# p2cled-001.net
KiCad netlist of a schematic drawn in EAGLE
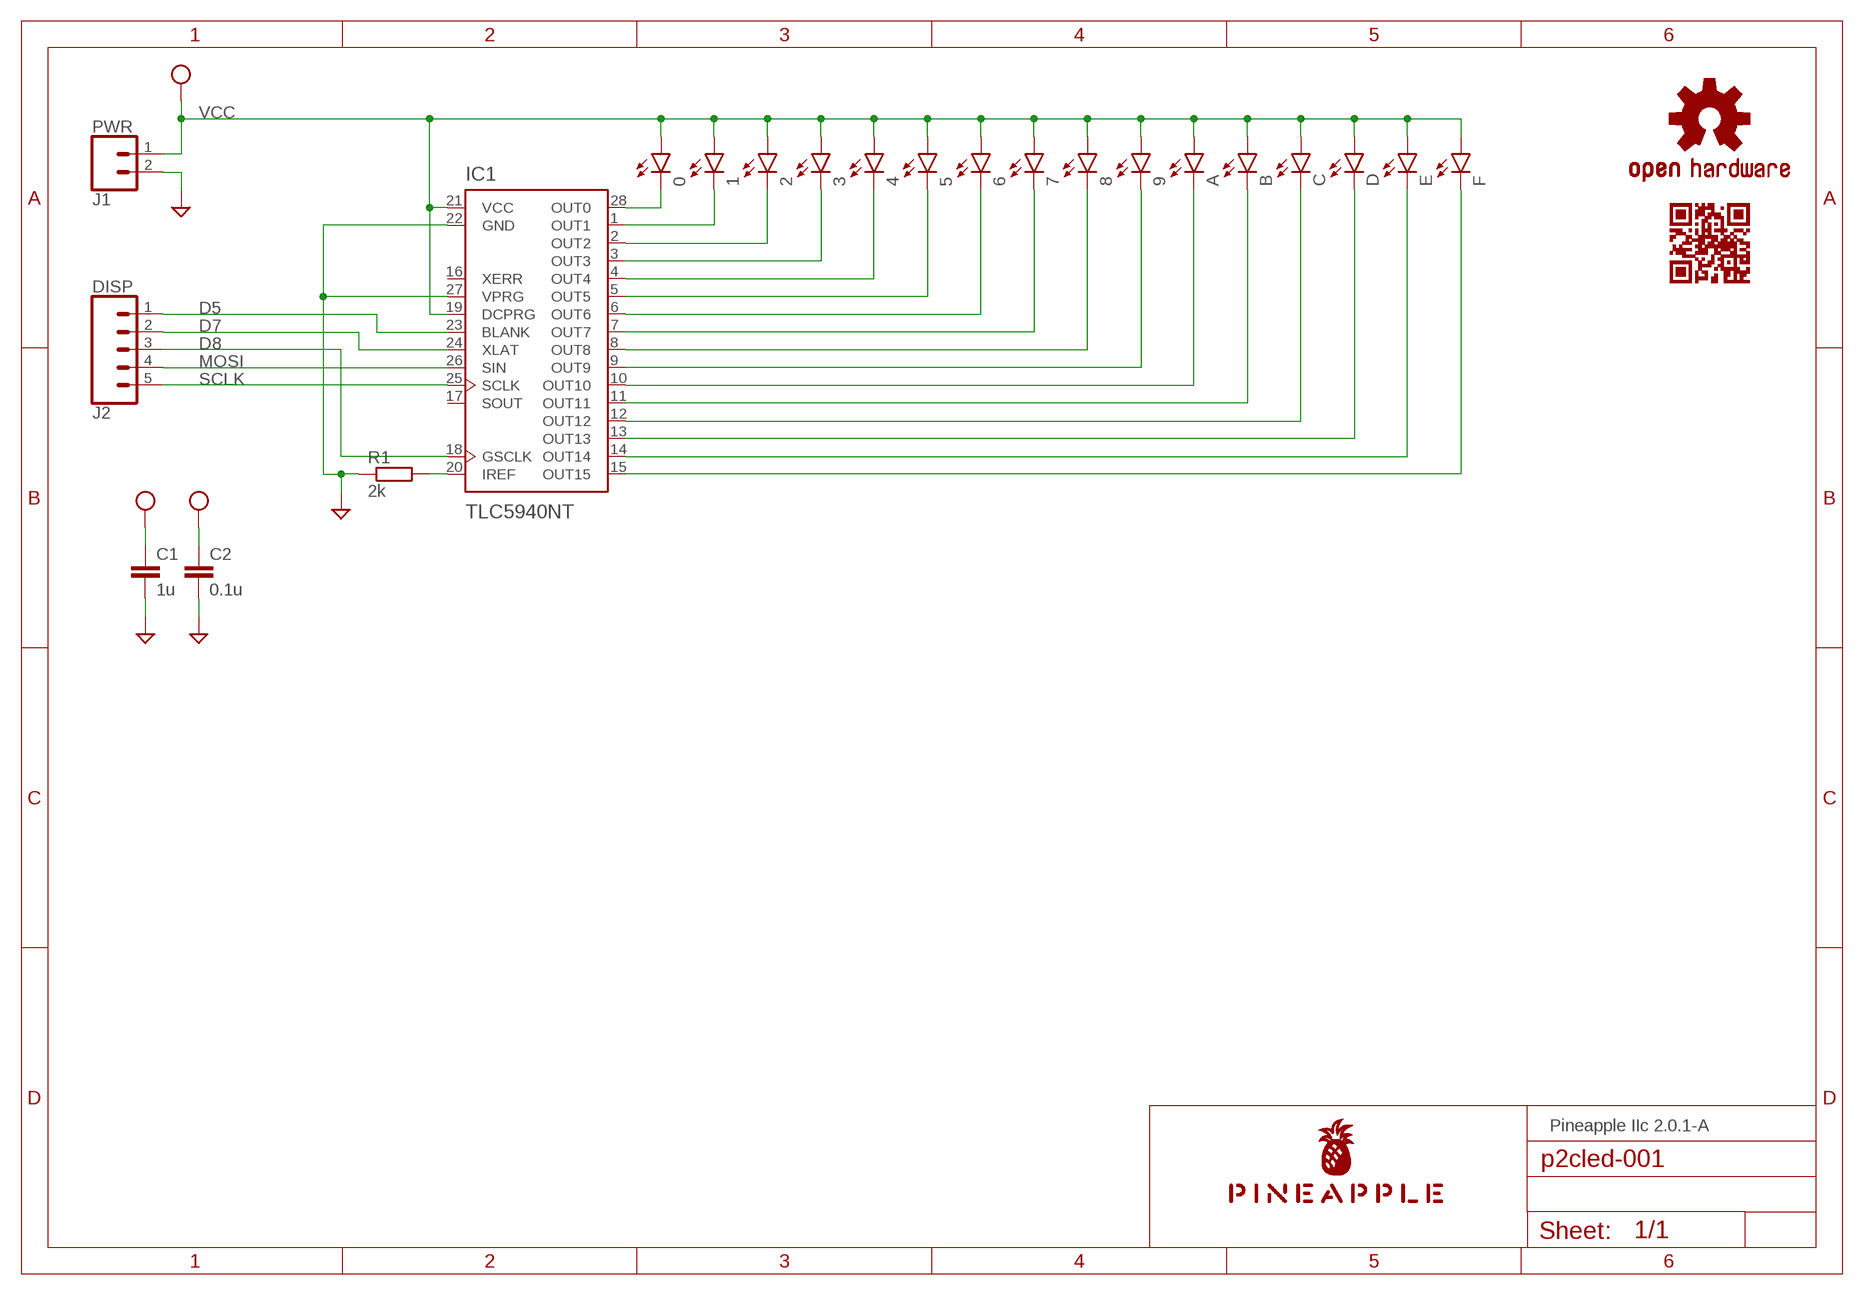
[diagram p0: schematic, sheet 1]

(export (version "E")
  (design (tool "Eeschema 10.0.6"))
  (components
    (comp (ref "0")
      (value "LEDB152")
      (footprint "eagle-import:Q62902-B152")
      (libsource (lib "eagle-import") (part "LEDB152"))
    )
    (comp (ref "1")
      (value "LEDB152")
      (footprint "eagle-import:Q62902-B152")
      (libsource (lib "eagle-import") (part "LEDB152"))
    )
    (comp (ref "2")
      (value "LEDB152")
      (footprint "eagle-import:Q62902-B152")
      (libsource (lib "eagle-import") (part "LEDB152"))
    )
    (comp (ref "3")
      (value "LEDB152")
      (footprint "eagle-import:Q62902-B152")
      (libsource (lib "eagle-import") (part "LEDB152"))
    )
    (comp (ref "4")
      (value "LEDB152")
      (footprint "eagle-import:Q62902-B152")
      (libsource (lib "eagle-import") (part "LEDB152"))
    )
    (comp (ref "5")
      (value "LEDB152")
      (footprint "eagle-import:Q62902-B152")
      (libsource (lib "eagle-import") (part "LEDB152"))
    )
    (comp (ref "6")
      (value "LEDB152")
      (footprint "eagle-import:Q62902-B152")
      (libsource (lib "eagle-import") (part "LEDB152"))
    )
    (comp (ref "7")
      (value "LEDB152")
      (footprint "eagle-import:Q62902-B152")
      (libsource (lib "eagle-import") (part "LEDB152"))
    )
    (comp (ref "8")
      (value "LEDB152")
      (footprint "eagle-import:Q62902-B152")
      (libsource (lib "eagle-import") (part "LEDB152"))
    )
    (comp (ref "9")
      (value "LEDB152")
      (footprint "eagle-import:Q62902-B152")
      (libsource (lib "eagle-import") (part "LEDB152"))
    )
    (comp (ref "A")
      (value "LEDB152")
      (footprint "eagle-import:Q62902-B152")
      (libsource (lib "eagle-import") (part "LEDB152"))
    )
    (comp (ref "B")
      (value "LEDB152")
      (footprint "eagle-import:Q62902-B152")
      (libsource (lib "eagle-import") (part "LEDB152"))
    )
    (comp (ref "C")
      (value "LEDB152")
      (footprint "eagle-import:Q62902-B152")
      (libsource (lib "eagle-import") (part "LEDB152"))
    )
    (comp (ref "C1")
      (value "1u")
      (footprint "eagle-import:C025-024X044")
      (libsource (lib "eagle-import") (part "C-EU025-024X044"))
    )
    (comp (ref "C2")
      (value "0.1u")
      (footprint "eagle-import:C025-024X044")
      (libsource (lib "eagle-import") (part "C-EU025-024X044"))
    )
    (comp (ref "D")
      (value "LEDB152")
      (footprint "eagle-import:Q62902-B152")
      (libsource (lib "eagle-import") (part "LEDB152"))
    )
    (comp (ref "E")
      (value "LEDB152")
      (footprint "eagle-import:Q62902-B152")
      (libsource (lib "eagle-import") (part "LEDB152"))
    )
    (comp (ref "F")
      (value "LEDB152")
      (footprint "eagle-import:Q62902-B152")
      (libsource (lib "eagle-import") (part "LEDB152"))
    )
    (comp (ref "IC1")
      (value "TLC5940NT")
      (footprint "eagle-import:DIL28-3")
      (libsource (lib "eagle-import") (part "TLC5940NT"))
    )
    (comp (ref "J1")
      (value "PWR")
      (footprint "eagle-import:JST-2-PTH")
      (libsource (lib "eagle-import") (part "CONN_02JST-PTH-2"))
    )
    (comp (ref "J2")
      (value "DISP")
      (footprint "eagle-import:JST-5-PTH")
      (libsource (lib "eagle-import") (part "CONN_05JST"))
    )
    (comp (ref "LOGO1")
      (value "OSHW-LOGOS-COPPER")
      (footprint "eagle-import:OSHW-LOGO-S_COPPER")
      (libsource (lib "eagle-import") (part "OSHW-LOGOS-COPPER"))
    )
    (comp (ref "R1")
      (value "2k")
      (footprint "eagle-import:0204_5")
      (libsource (lib "eagle-import") (part "R-EU_0204/5"))
    )
    (comp (ref "U$1")
      (value "PINEAPPLE450_SILK")
      (footprint "eagle-import:PINEAPPLE450_SILK")
      (libsource (lib "eagle-import") (part "PINEAPPLE450_SILK"))
    )
    (comp (ref "U$4")
      (value "CARDQRCODE450_SILK")
      (footprint "eagle-import:CARDQRCODE450_SILK")
      (libsource (lib "eagle-import") (part "CARDQRCODE450_SILK"))
    )
  )
  (nets
    (net (code "1") (name "/D5") (class "Default")
      (node (ref "IC1") (pin "23") (pinfunction "BLANK_23") (pintype "input"))
      (node (ref "J2") (pin "1") (pinfunction "1_1") (pintype "passive"))
    )
    (net (code "2") (name "/D7") (class "Default")
      (node (ref "IC1") (pin "24") (pinfunction "XLAT_24") (pintype "input"))
      (node (ref "J2") (pin "2") (pinfunction "2_2") (pintype "passive"))
    )
    (net (code "3") (name "/D8") (class "Default")
      (node (ref "IC1") (pin "18") (pinfunction "GSCLK_18") (pintype "input"))
      (node (ref "J2") (pin "3") (pinfunction "3_3") (pintype "passive"))
    )
    (net (code "4") (name "/MOSI") (class "Default")
      (node (ref "IC1") (pin "26") (pinfunction "SIN_26") (pintype "input"))
      (node (ref "J2") (pin "4") (pinfunction "4_4") (pintype "passive"))
    )
    (net (code "5") (name "/SCLK") (class "Default")
      (node (ref "IC1") (pin "25") (pinfunction "SCLK_25") (pintype "input"))
      (node (ref "J2") (pin "5") (pinfunction "5_5") (pintype "passive"))
    )
    (net (code "6") (name "GND") (class "Default")
      (node (ref "C1") (pin "2") (pinfunction "2_2") (pintype "passive"))
      (node (ref "C2") (pin "2") (pinfunction "2_2") (pintype "passive"))
      (node (ref "IC1") (pin "22") (pinfunction "GND_22") (pintype "power_in"))
      (node (ref "IC1") (pin "27") (pinfunction "VPRG_27") (pintype "input"))
      (node (ref "J1") (pin "2") (pinfunction "2_2") (pintype "passive"))
      (node (ref "R1") (pin "1") (pinfunction "1_1") (pintype "passive"))
    )
    (net (code "7") (name "Net-(0-C)") (class "Default")
      (node (ref "0") (pin "K") (pinfunction "C_K") (pintype "passive"))
      (node (ref "IC1") (pin "28") (pinfunction "OUT0_28") (pintype "output"))
    )
    (net (code "8") (name "Net-(1-C)") (class "Default")
      (node (ref "1") (pin "K") (pinfunction "C_K") (pintype "passive"))
      (node (ref "IC1") (pin "1") (pinfunction "OUT1_1") (pintype "output"))
    )
    (net (code "9") (name "Net-(2-C)") (class "Default")
      (node (ref "2") (pin "K") (pinfunction "C_K") (pintype "passive"))
      (node (ref "IC1") (pin "2") (pinfunction "OUT2_2") (pintype "output"))
    )
    (net (code "10") (name "Net-(3-C)") (class "Default")
      (node (ref "3") (pin "K") (pinfunction "C_K") (pintype "passive"))
      (node (ref "IC1") (pin "3") (pinfunction "OUT3_3") (pintype "output"))
    )
    (net (code "11") (name "Net-(4-C)") (class "Default")
      (node (ref "4") (pin "K") (pinfunction "C_K") (pintype "passive"))
      (node (ref "IC1") (pin "4") (pinfunction "OUT4_4") (pintype "output"))
    )
    (net (code "12") (name "Net-(5-C)") (class "Default")
      (node (ref "5") (pin "K") (pinfunction "C_K") (pintype "passive"))
      (node (ref "IC1") (pin "5") (pinfunction "OUT5_5") (pintype "output"))
    )
    (net (code "13") (name "Net-(6-C)") (class "Default")
      (node (ref "6") (pin "K") (pinfunction "C_K") (pintype "passive"))
      (node (ref "IC1") (pin "6") (pinfunction "OUT6_6") (pintype "output"))
    )
    (net (code "14") (name "Net-(7-C)") (class "Default")
      (node (ref "7") (pin "K") (pinfunction "C_K") (pintype "passive"))
      (node (ref "IC1") (pin "7") (pinfunction "OUT7_7") (pintype "output"))
    )
    (net (code "15") (name "Net-(8-C)") (class "Default")
      (node (ref "8") (pin "K") (pinfunction "C_K") (pintype "passive"))
      (node (ref "IC1") (pin "8") (pinfunction "OUT8_8") (pintype "output"))
    )
    (net (code "16") (name "Net-(9-C)") (class "Default")
      (node (ref "9") (pin "K") (pinfunction "C_K") (pintype "passive"))
      (node (ref "IC1") (pin "9") (pinfunction "OUT9_9") (pintype "output"))
    )
    (net (code "17") (name "Net-(A-C)") (class "Default")
      (node (ref "A") (pin "K") (pinfunction "C_K") (pintype "passive"))
      (node (ref "IC1") (pin "10") (pinfunction "OUT10_10") (pintype "output"))
    )
    (net (code "18") (name "Net-(B-C)") (class "Default")
      (node (ref "B") (pin "K") (pinfunction "C_K") (pintype "passive"))
      (node (ref "IC1") (pin "11") (pinfunction "OUT11_11") (pintype "output"))
    )
    (net (code "19") (name "Net-(C-C)") (class "Default")
      (node (ref "C") (pin "K") (pinfunction "C_K") (pintype "passive"))
      (node (ref "IC1") (pin "12") (pinfunction "OUT12_12") (pintype "output"))
    )
    (net (code "20") (name "Net-(D-C)") (class "Default")
      (node (ref "D") (pin "K") (pinfunction "C_K") (pintype "passive"))
      (node (ref "IC1") (pin "13") (pinfunction "OUT13_13") (pintype "output"))
    )
    (net (code "21") (name "Net-(E-C)") (class "Default")
      (node (ref "E") (pin "K") (pinfunction "C_K") (pintype "passive"))
      (node (ref "IC1") (pin "14") (pinfunction "OUT14_14") (pintype "output"))
    )
    (net (code "22") (name "Net-(F-C)") (class "Default")
      (node (ref "F") (pin "K") (pinfunction "C_K") (pintype "passive"))
      (node (ref "IC1") (pin "15") (pinfunction "OUT15_15") (pintype "output"))
    )
    (net (code "23") (name "Net-(IC1-IREF)") (class "Default")
      (node (ref "IC1") (pin "20") (pinfunction "IREF_20") (pintype "passive"))
      (node (ref "R1") (pin "2") (pinfunction "2_2") (pintype "passive"))
    )
    (net (code "24") (name "VCC") (class "Default")
      (node (ref "0") (pin "A") (pinfunction "A_A") (pintype "passive"))
      (node (ref "1") (pin "A") (pinfunction "A_A") (pintype "passive"))
      (node (ref "2") (pin "A") (pinfunction "A_A") (pintype "passive"))
      (node (ref "3") (pin "A") (pinfunction "A_A") (pintype "passive"))
      (node (ref "4") (pin "A") (pinfunction "A_A") (pintype "passive"))
      (node (ref "5") (pin "A") (pinfunction "A_A") (pintype "passive"))
      (node (ref "6") (pin "A") (pinfunction "A_A") (pintype "passive"))
      (node (ref "7") (pin "A") (pinfunction "A_A") (pintype "passive"))
      (node (ref "8") (pin "A") (pinfunction "A_A") (pintype "passive"))
      (node (ref "9") (pin "A") (pinfunction "A_A") (pintype "passive"))
      (node (ref "A") (pin "A") (pinfunction "A_A") (pintype "passive"))
      (node (ref "B") (pin "A") (pinfunction "A_A") (pintype "passive"))
      (node (ref "C") (pin "A") (pinfunction "A_A") (pintype "passive"))
      (node (ref "C1") (pin "1") (pinfunction "1_1") (pintype "passive"))
      (node (ref "C2") (pin "1") (pinfunction "1_1") (pintype "passive"))
      (node (ref "D") (pin "A") (pinfunction "A_A") (pintype "passive"))
      (node (ref "E") (pin "A") (pinfunction "A_A") (pintype "passive"))
      (node (ref "F") (pin "A") (pinfunction "A_A") (pintype "passive"))
      (node (ref "IC1") (pin "19") (pinfunction "DCPRG_19") (pintype "input"))
      (node (ref "IC1") (pin "21") (pinfunction "VCC_21") (pintype "power_in"))
      (node (ref "J1") (pin "1") (pinfunction "1_1") (pintype "passive"))
    )
    (net (code "25") (name "unconnected-(IC1-SOUT-Pad17)") (class "Default")
      (node (ref "IC1") (pin "17") (pinfunction "SOUT_17") (pintype "output"))
    )
    (net (code "26") (name "unconnected-(IC1-XERR-Pad16)") (class "Default")
      (node (ref "IC1") (pin "16") (pinfunction "XERR_16") (pintype "output"))
    )
  )
)
